# Data_Conversion_TopBoard.net
KiCad netlist of a schematic drawn in Altium Designer
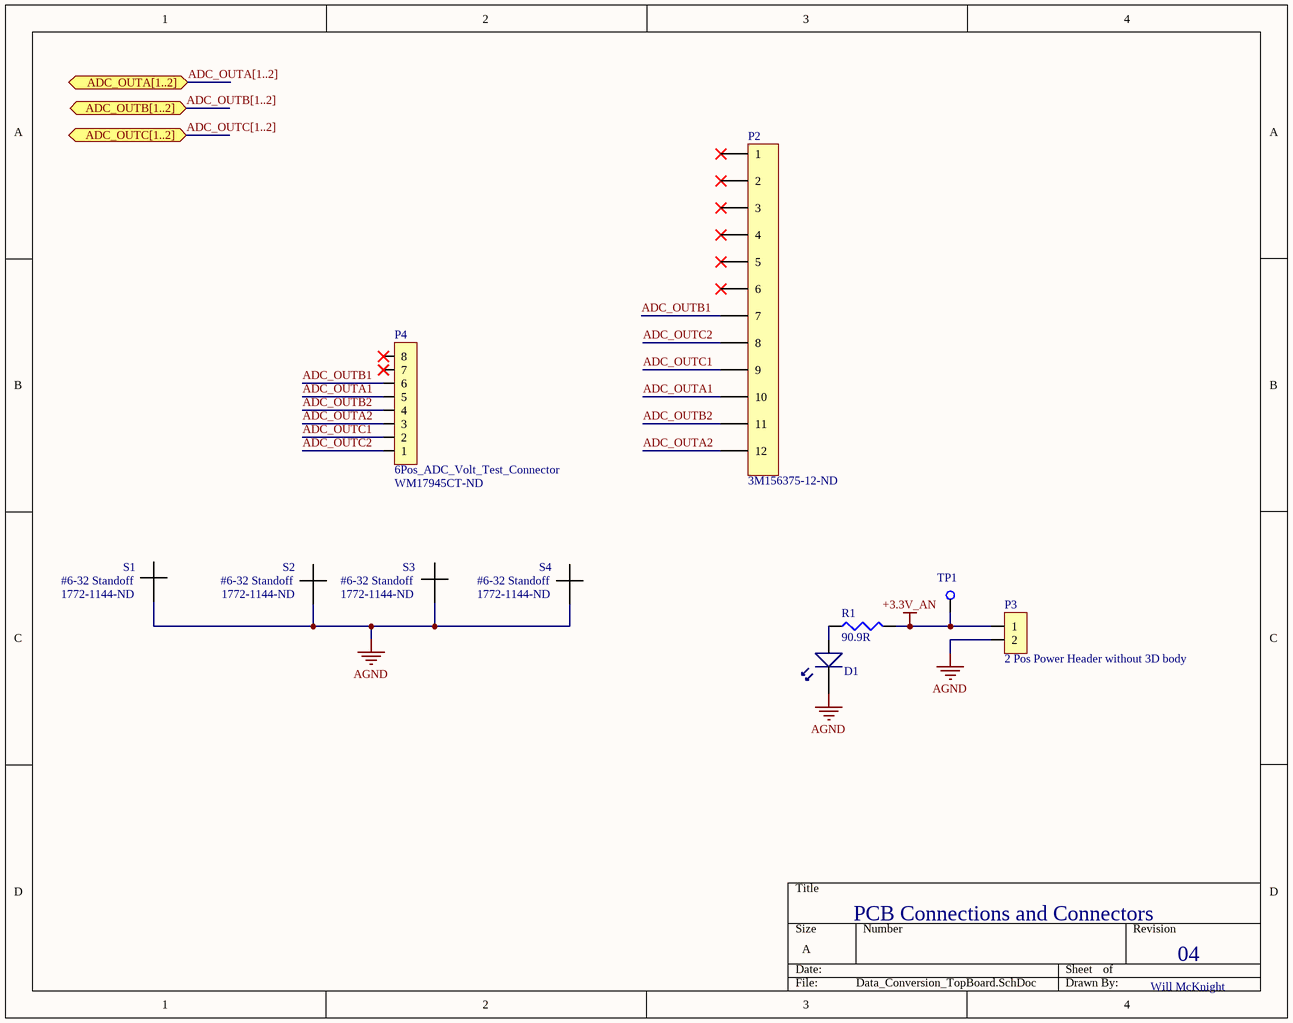
[diagram p0: Data_Conversion_TopBoard.SchDoc]

(export (version "E")
  (design (tool "Eeschema 10.0.6"))
  (components
    (comp (ref "D1")
      (value "LED")
      (footprint "Green_SMD_LED")
      (fields
        (field (name "MANUFACTURER") "Dialight")
        (field (name "MANUFACTURER PART NUMBER") "5988070107F")
      )
      (libsource (lib "Schematic_Library") (part "GREEN_LED"))
    )
    (comp (ref "P2")
      (value "12POS Dual Header W/O 3D Body")
      (footprint "12POS Dual Header W/O 3D Body")
      (description "Connector Header Through Hole 12 position 0.100\" (2.54mm)")
      (fields
        (field (name "MANUFACTURER") "3M")
        (field (name "MANUFACTURER PART NUMBER") "929715-06-06-EU")
        (field (name "SUPPLIER PART NUMBER 1") "3M156375-12-ND")
      )
      (libsource (lib "Schematic_Library") (part "12POS Dual Header W/O 3D Body"))
    )
    (comp (ref "P3")
      (value "2 Pos Power Header without 3D body")
      (footprint "2 Pos Power Header - duplicate")
      (libsource (lib "Schematic_Library") (part "2 Pos Power Header without 3D body"))
    )
    (comp (ref "P4")
      (value "6Pos_ADC_Volt_Test_Connector")
      (footprint "6POS_ADC_Volt_TEST")
      (description "Connector Header Surface Mount, Right Angle 6 position 0.079\" (2.00mm)")
      (fields
        (field (name "MANUFACTURER") "Molex")
        (field (name "MANUFACTURER PART NUMBER") "5055780671")
        (field (name "SUPPLIER PART NUMBER 1") "WM17945CT-ND")
      )
      (libsource (lib "Schematic_Library") (part "6Pos_ADC_Volt_Test_Connector"))
    )
    (comp (ref "R1")
      (value "Green")
      (footprint "Green_LED_Resistor_90.9")
      (fields
        (field (name "MANUFACTURER") "Panasonic")
        (field (name "MANUFACTURER PART NUMBER") "ERJ-1GNF90R9C")
        (field (name "TOLERANCE") "1%")
        (field (name "RESISTANCE") "90.9R")
      )
      (libsource (lib "Schematic_Library") (part "Green_LED_Res"))
    )
    (comp (ref "S1")
      (value "#6-32 Standoff")
      (footprint "#6-32 Stand Off")
      (description "Hex Standoff for Thermistor Boards")
      (fields
        (field (name "MANUFACTURER") "RAF")
        (field (name "MANUFACTURER PART NUMBER") "2102T-632-AL-7")
        (field (name "SUPPLIER PART NUMBER 1") "1772-1144-ND")
      )
      (libsource (lib "Schematic_Library") (part "#6-32 Standoff"))
    )
    (comp (ref "S2")
      (value "#6-32 Standoff")
      (footprint "#6-32 Stand Off")
      (description "Hex Standoff for Thermistor Boards")
      (fields
        (field (name "MANUFACTURER") "RAF")
        (field (name "MANUFACTURER PART NUMBER") "2102T-632-AL-7")
        (field (name "SUPPLIER PART NUMBER 1") "1772-1144-ND")
      )
      (libsource (lib "Schematic_Library") (part "#6-32 Standoff"))
    )
    (comp (ref "S3")
      (value "#6-32 Standoff")
      (footprint "#6-32 Stand Off")
      (description "Hex Standoff for Thermistor Boards")
      (fields
        (field (name "MANUFACTURER") "RAF")
        (field (name "MANUFACTURER PART NUMBER") "2102T-632-AL-7")
        (field (name "SUPPLIER PART NUMBER 1") "1772-1144-ND")
      )
      (libsource (lib "Schematic_Library") (part "#6-32 Standoff"))
    )
    (comp (ref "S4")
      (value "#6-32 Standoff")
      (footprint "#6-32 Stand Off")
      (description "Hex Standoff for Thermistor Boards")
      (fields
        (field (name "MANUFACTURER") "RAF")
        (field (name "MANUFACTURER PART NUMBER") "2102T-632-AL-7")
        (field (name "SUPPLIER PART NUMBER 1") "1772-1144-ND")
      )
      (libsource (lib "Schematic_Library") (part "#6-32 Standoff"))
    )
    (comp (ref "TP1")
      (value "Test Point")
      (footprint "Test Point")
      (libsource (lib "Schematic_Library") (part "Test Point"))
    )
  )
  (nets
    (net (code "1") (name "+3.3V_AN") (class "Default")
      (node (ref "P3") (pin "1") (pinfunction "1_1") (pintype "passive"))
      (node (ref "R1") (pin "2") (pinfunction "2_2") (pintype "passive"))
      (node (ref "TP1") (pin "1") (pinfunction "1_1") (pintype "passive"))
    )
    (net (code "2") (name "/ADC_OUTA1") (class "Default")
      (node (ref "P2") (pin "10") (pinfunction "10_10") (pintype "passive"))
      (node (ref "P4") (pin "5") (pinfunction "5_5") (pintype "passive"))
    )
    (net (code "3") (name "/ADC_OUTA2") (class "Default")
      (node (ref "P2") (pin "12") (pinfunction "12_12") (pintype "passive"))
      (node (ref "P4") (pin "3") (pinfunction "3_3") (pintype "passive"))
    )
    (net (code "5") (name "/ADC_OUTB1") (class "Default")
      (node (ref "P2") (pin "7") (pinfunction "7_7") (pintype "passive"))
      (node (ref "P4") (pin "6") (pinfunction "6_6") (pintype "passive"))
    )
    (net (code "6") (name "/ADC_OUTB2") (class "Default")
      (node (ref "P2") (pin "11") (pinfunction "11_11") (pintype "passive"))
      (node (ref "P4") (pin "4") (pinfunction "4_4") (pintype "passive"))
    )
    (net (code "8") (name "/ADC_OUTC1") (class "Default")
      (node (ref "P2") (pin "9") (pinfunction "9_9") (pintype "passive"))
      (node (ref "P4") (pin "2") (pinfunction "2_2") (pintype "passive"))
    )
    (net (code "9") (name "/ADC_OUTC2") (class "Default")
      (node (ref "P2") (pin "8") (pinfunction "8_8") (pintype "passive"))
      (node (ref "P4") (pin "1") (pinfunction "1_1") (pintype "passive"))
    )
    (net (code "11") (name "AGND") (class "Default")
      (node (ref "D1") (pin "1") (pinfunction "1_1") (pintype "passive"))
      (node (ref "P3") (pin "2") (pinfunction "2_2") (pintype "passive"))
      (node (ref "S1") (pin "1") (pinfunction "1_1") (pintype "passive"))
      (node (ref "S2") (pin "1") (pinfunction "1_1") (pintype "passive"))
      (node (ref "S3") (pin "1") (pinfunction "1_1") (pintype "passive"))
      (node (ref "S4") (pin "1") (pinfunction "1_1") (pintype "passive"))
    )
    (net (code "12") (name "Net-(D1-Pad2)") (class "Default")
      (node (ref "D1") (pin "2") (pinfunction "2_2") (pintype "passive"))
      (node (ref "R1") (pin "1") (pinfunction "1_1") (pintype "passive"))
    )
    (net (code "13") (name "unconnected-(P2-Pad1)") (class "Default")
      (node (ref "P2") (pin "1") (pinfunction "1_1") (pintype "passive+no_connect"))
    )
    (net (code "14") (name "unconnected-(P2-Pad2)") (class "Default")
      (node (ref "P2") (pin "2") (pinfunction "2_2") (pintype "passive+no_connect"))
    )
    (net (code "15") (name "unconnected-(P2-Pad3)") (class "Default")
      (node (ref "P2") (pin "3") (pinfunction "3_3") (pintype "passive+no_connect"))
    )
    (net (code "16") (name "unconnected-(P2-Pad4)") (class "Default")
      (node (ref "P2") (pin "4") (pinfunction "4_4") (pintype "passive+no_connect"))
    )
    (net (code "17") (name "unconnected-(P2-Pad5)") (class "Default")
      (node (ref "P2") (pin "5") (pinfunction "5_5") (pintype "passive+no_connect"))
    )
    (net (code "18") (name "unconnected-(P2-Pad6)") (class "Default")
      (node (ref "P2") (pin "6") (pinfunction "6_6") (pintype "passive+no_connect"))
    )
    (net (code "19") (name "unconnected-(P4-Pad7)") (class "Default")
      (node (ref "P4") (pin "7") (pinfunction "7_7") (pintype "passive+no_connect"))
    )
    (net (code "20") (name "unconnected-(P4-Pad8)") (class "Default")
      (node (ref "P4") (pin "8") (pinfunction "8_8") (pintype "passive+no_connect"))
    )
  )
)
